# SCH_VE-GENERATOR_2026-01-31.net
KiCad netlist of a schematic drawn in EasyEDA
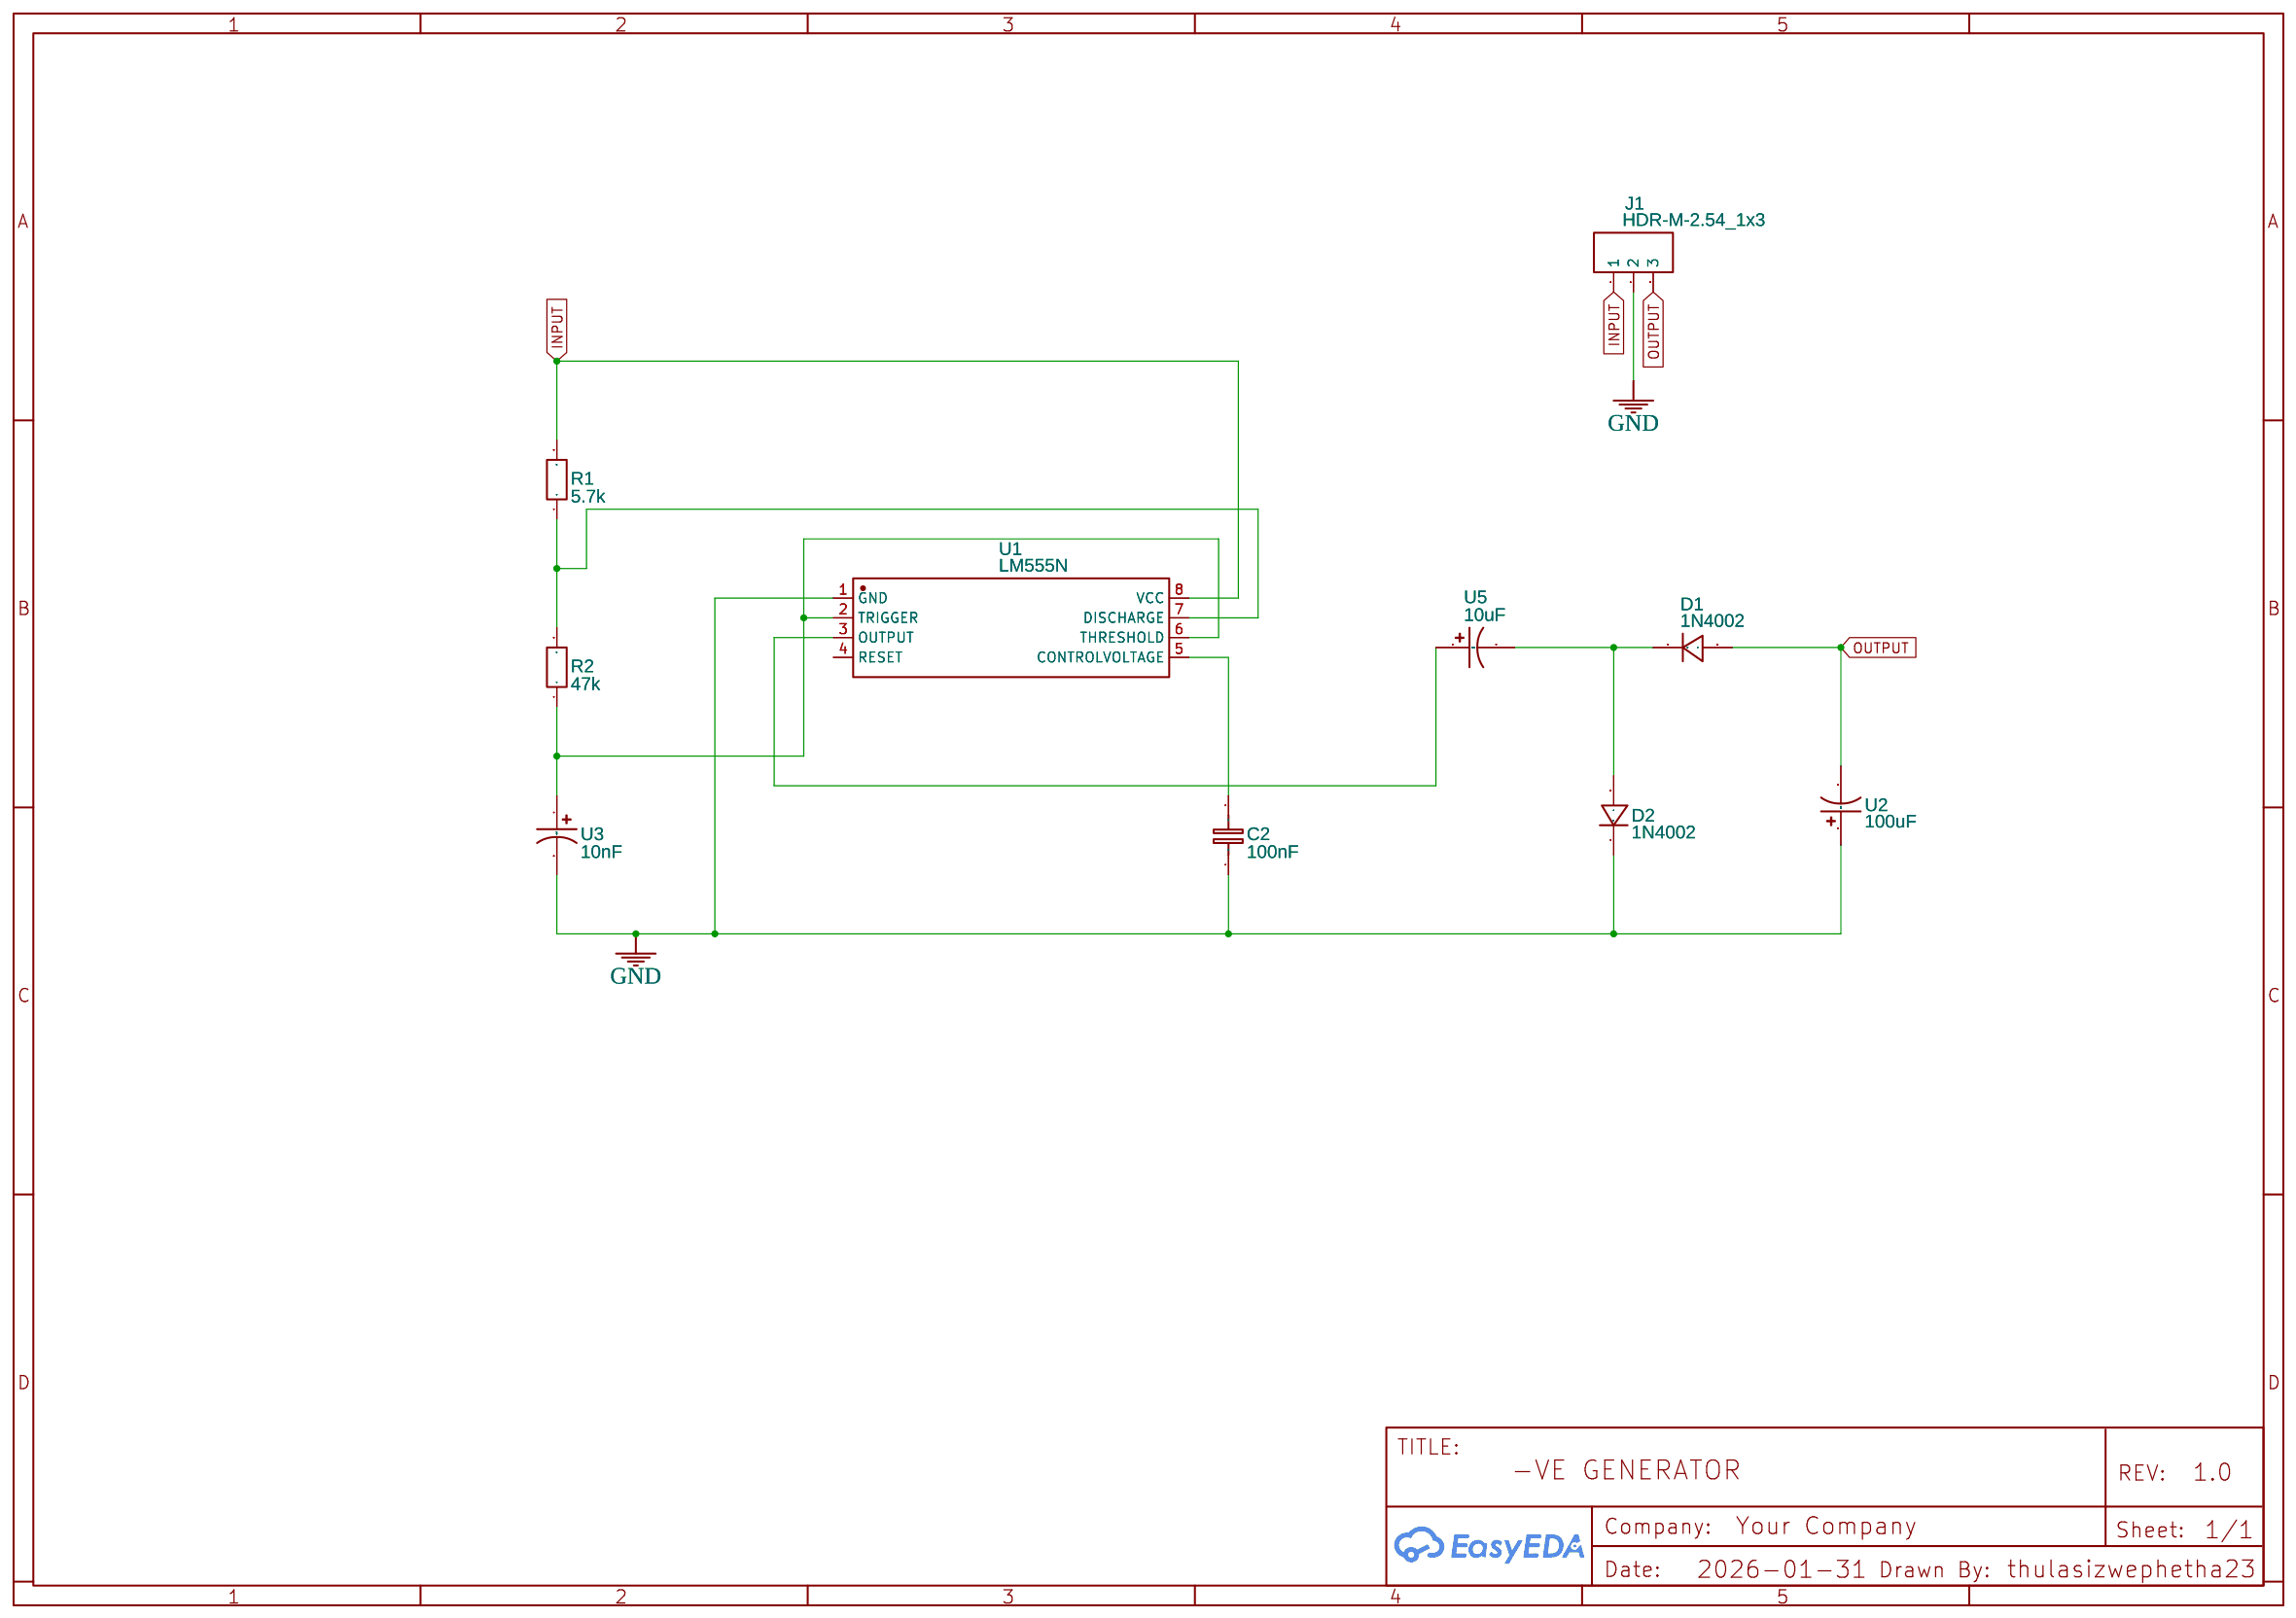
[diagram p0: schematic sheet]

(export (version "E")
  (design (tool "Eeschema 10.0.6"))
  (components
    (comp (ref "C2") (value "100nF") (libsource (lib "") (part "C_RAD-0.1_EU")))
    (comp (ref "D1")
      (value "1N4002")
      (fields (field (name "Manufacturer") "GW(唯圣)"))
      (libsource (lib "") (part "1N4002_1"))
    )
    (comp (ref "D2")
      (value "1N4002")
      (fields (field (name "Manufacturer") "GW(唯圣)"))
      (libsource (lib "") (part "1N4002"))
    )
    (comp (ref "J1") (value "HDR-M-2.54_1x3") (libsource (lib "") (part "HDR-M-2.54_1x3")))
    (comp (ref "R1") (value "5.7k") (libsource (lib "") (part "R_AXIAL-0.3_EU")))
    (comp (ref "R2") (value "47k") (libsource (lib "") (part "R_AXIAL-0.3_EU")))
    (comp (ref "U1")
      (value "LM555N")
      (fields (field (name "Manufacturer") "HGSEMI(华冠)"))
      (libsource (lib "") (part "LM555N"))
    )
    (comp (ref "U2")
      (value "100uF")
      (fields (field (name "Manufacturer Part") "Capacitor_THT:CP_Radial_D8.0mm_P2.50mm"))
      (libsource (lib "") (part "CAPACITOR_THT{colon}CP_RADIAL_D8.0MM_P2.50MM_2"))
    )
    (comp (ref "U3")
      (value "10nF")
      (fields (field (name "Manufacturer Part") "Capacitor_THT:CP_Radial_D8.0mm_P2.50mm"))
      (libsource (lib "") (part "CAPACITOR_THT{colon}CP_RADIAL_D8.0MM_P2.50MM_1"))
    )
    (comp (ref "U5")
      (value "10uF")
      (fields (field (name "Manufacturer Part") "Capacitor_THT:CP_Radial_D8.0mm_P2.50mm"))
      (libsource (lib "") (part "CAPACITOR_THT{colon}CP_RADIAL_D8.0MM_P2.50MM"))
    )
  )
  (nets
    (net (code "1") (name "GND") (class "Default")
      (node (ref "C2") (pin "1") (pinfunction "1_1") (pintype "unspecified"))
      (node (ref "D2") (pin "1") (pinfunction "C_1") (pintype "unspecified"))
      (node (ref "J1") (pin "2") (pinfunction "2_2") (pintype "input"))
      (node (ref "U1") (pin "1") (pinfunction "GND_1") (pintype "unspecified"))
      (node (ref "U2") (pin "1") (pinfunction "1_1") (pintype "unspecified"))
      (node (ref "U3") (pin "2") (pinfunction "2_2") (pintype "unspecified"))
    )
    (net (code "2") (name "INPUT") (class "Default")
      (node (ref "J1") (pin "1") (pinfunction "1_1") (pintype "input"))
      (node (ref "R1") (pin "2") (pinfunction "2_2") (pintype "unspecified"))
      (node (ref "U1") (pin "8") (pinfunction "VCC_8") (pintype "unspecified"))
    )
    (net (code "3") (name "Net-(D1-C)") (class "Default")
      (node (ref "D1") (pin "1") (pinfunction "C_1") (pintype "unspecified"))
      (node (ref "D2") (pin "2") (pinfunction "A_2") (pintype "unspecified"))
      (node (ref "U5") (pin "2") (pinfunction "2_2") (pintype "unspecified"))
    )
    (net (code "4") (name "Net-(U1-CONTROLVOLTAGE)") (class "Default")
      (node (ref "C2") (pin "2") (pinfunction "2_2") (pintype "unspecified"))
      (node (ref "U1") (pin "5") (pinfunction "CONTROLVOLTAGE_5") (pintype "unspecified"))
    )
    (net (code "5") (name "Net-(U1-DISCHARGE)") (class "Default")
      (node (ref "R1") (pin "1") (pinfunction "1_1") (pintype "unspecified"))
      (node (ref "R2") (pin "2") (pinfunction "2_2") (pintype "unspecified"))
      (node (ref "U1") (pin "7") (pinfunction "DISCHARGE_7") (pintype "unspecified"))
    )
    (net (code "6") (name "Net-(U1-OUTPUT)") (class "Default")
      (node (ref "U1") (pin "3") (pinfunction "OUTPUT_3") (pintype "unspecified"))
      (node (ref "U5") (pin "1") (pinfunction "1_1") (pintype "unspecified"))
    )
    (net (code "7") (name "Net-(U1-THRESHOLD)") (class "Default")
      (node (ref "R2") (pin "1") (pinfunction "1_1") (pintype "unspecified"))
      (node (ref "U1") (pin "2") (pinfunction "TRIGGER_2") (pintype "unspecified"))
      (node (ref "U1") (pin "6") (pinfunction "THRESHOLD_6") (pintype "unspecified"))
      (node (ref "U3") (pin "1") (pinfunction "1_1") (pintype "unspecified"))
    )
    (net (code "8") (name "OUTPUT") (class "Default")
      (node (ref "D1") (pin "2") (pinfunction "A_2") (pintype "unspecified"))
      (node (ref "J1") (pin "3") (pinfunction "3_3") (pintype "input"))
      (node (ref "U2") (pin "2") (pinfunction "2_2") (pintype "unspecified"))
    )
    (net (code "9") (name "unconnected-(U1-RESET-Pad4)") (class "Default")
      (node (ref "U1") (pin "4") (pinfunction "RESET_4") (pintype "unspecified"))
    )
  )
)
